# C2Sv0_-_Adaptor_TopLevel.net
KiCad netlist of a schematic drawn in Altium Designer
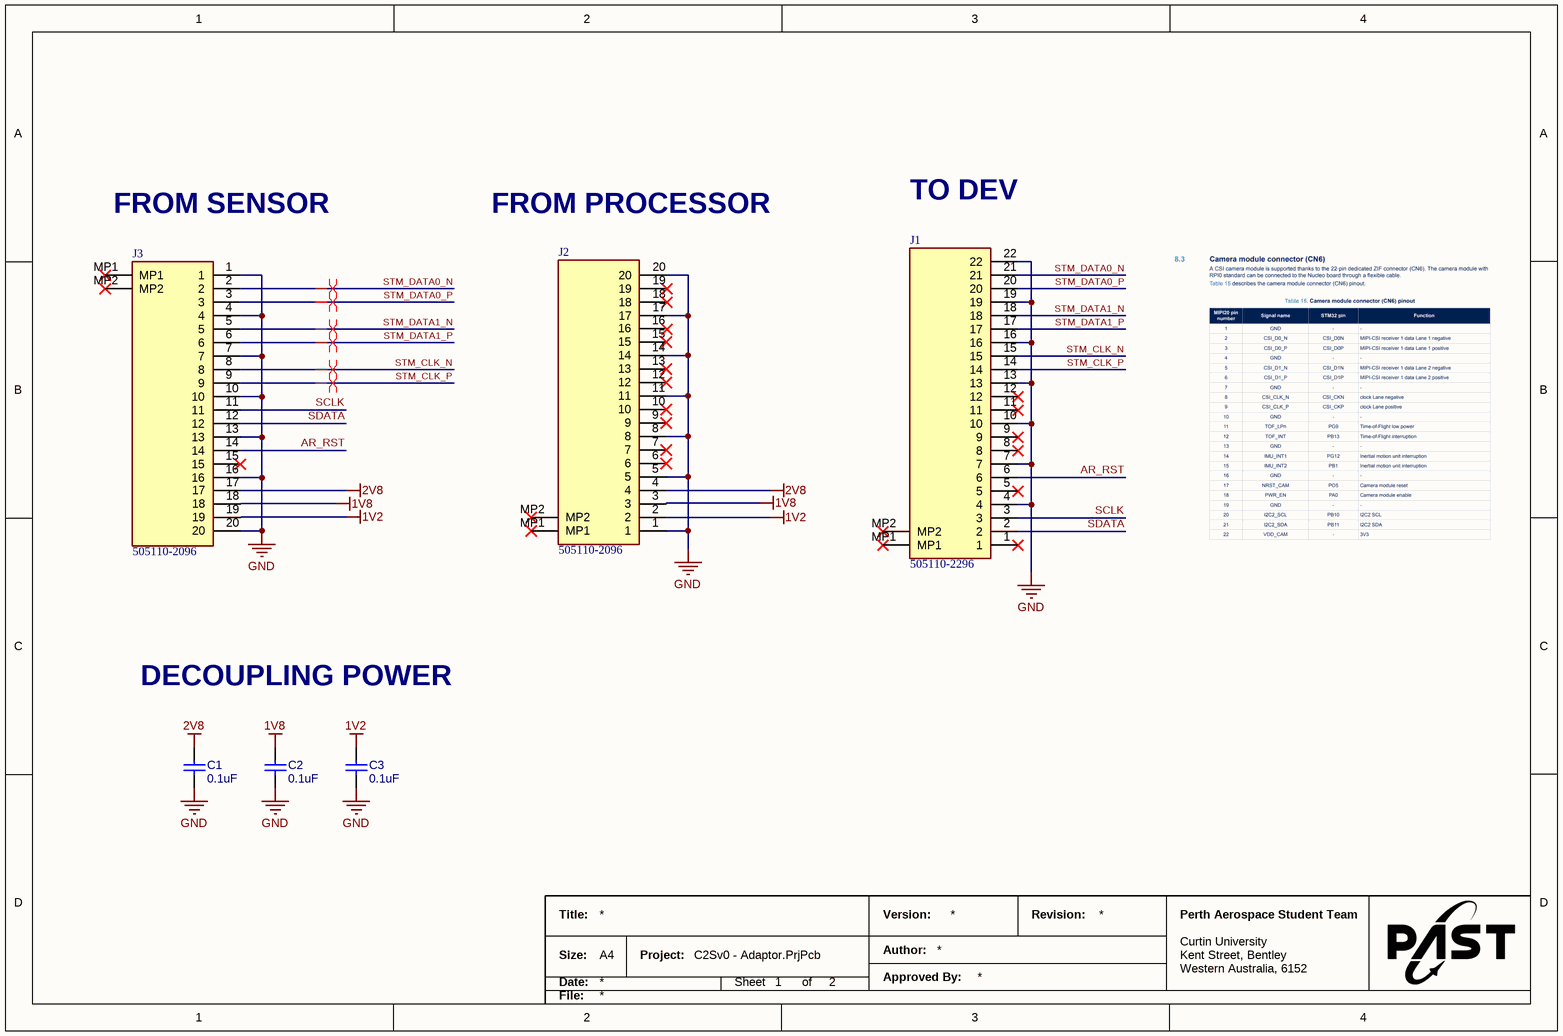
[diagram p0: C2Sv0 - Adaptor_TopLevel.SchDoc]

(export (version "E")
  (design (tool "Eeschema 10.0.6"))
  (components
    (comp (ref "C1")
      (value "0.1uF")
      (footprint "C0603")
      (description "Capacitor, MLCC, 100nF, 6V3, X5R, 10%, 0603, T=0,8mm")
      (fields
        (field (name "MANUFACTURER PART NUMBER") "CC0603KRX5R5BB104")
        (field (name "MANUFACTURER") "YAGEO")
        (field (name "PROVIDED_BY") "SUBCO")
      )
      (libsource (lib "Perth Aerospace Student Team") (part "CMP-035-000015-1"))
    )
    (comp (ref "C2")
      (value "0.1uF")
      (footprint "C0603")
      (description "Capacitor, MLCC, 100nF, 6V3, X5R, 10%, 0603, T=0,8mm")
      (fields
        (field (name "MANUFACTURER PART NUMBER") "CC0603KRX5R5BB104")
        (field (name "MANUFACTURER") "YAGEO")
        (field (name "PROVIDED_BY") "SUBCO")
      )
      (libsource (lib "Perth Aerospace Student Team") (part "CMP-035-000015-1"))
    )
    (comp (ref "C3")
      (value "0.1uF")
      (footprint "C0603")
      (description "Capacitor, MLCC, 100nF, 6V3, X5R, 10%, 0603, T=0,8mm")
      (fields
        (field (name "MANUFACTURER PART NUMBER") "CC0603KRX5R5BB104")
        (field (name "MANUFACTURER") "YAGEO")
        (field (name "PROVIDED_BY") "SUBCO")
      )
      (libsource (lib "Perth Aerospace Student Team") (part "CMP-035-000015-1"))
    )
    (comp (ref "J1")
      (value "505110-2296")
      (footprint "C2Sv0 - Adaptor:505110-2296")
      (description "Connector")
      (fields (field (name "MOUSER PART NUMBER") "538-505110-2296"))
      (libsource (lib "C2Sv0 - Adaptor") (part "505110-2296"))
    )
    (comp (ref "J2")
      (value "505110-2096")
      (footprint "505110-2096")
      (description "Connector")
      (fields (field (name "MOUSER PART NUMBER") "538-505110-2096"))
      (libsource (lib "C2Sv0 - Adaptor") (part "505110-2096"))
    )
    (comp (ref "J3")
      (value "505110-2096")
      (footprint "505110-2096")
      (description "Connector")
      (fields (field (name "MOUSER PART NUMBER") "538-505110-2096"))
      (libsource (lib "") (part "505110-2096_1"))
    )
  )
  (nets
    (net (code "1") (name "/AR_RST") (class "Default")
      (node (ref "J1") (pin "6") (pinfunction "6_6") (pintype "passive"))
      (node (ref "J3") (pin "14") (pinfunction "14_14") (pintype "passive"))
    )
    (net (code "2") (name "/SCLK") (class "Default")
      (node (ref "J1") (pin "3") (pinfunction "3_3") (pintype "passive"))
      (node (ref "J3") (pin "11") (pinfunction "11_11") (pintype "passive"))
    )
    (net (code "3") (name "/SDATA") (class "Default")
      (node (ref "J1") (pin "2") (pinfunction "2_2") (pintype "passive"))
      (node (ref "J3") (pin "12") (pinfunction "12_12") (pintype "passive"))
    )
    (net (code "4") (name "/STM_CLK_N") (class "Default")
      (node (ref "J1") (pin "15") (pinfunction "15_15") (pintype "passive"))
      (node (ref "J3") (pin "8") (pinfunction "8_8") (pintype "passive"))
    )
    (net (code "5") (name "/STM_CLK_P") (class "Default")
      (node (ref "J1") (pin "14") (pinfunction "14_14") (pintype "passive"))
      (node (ref "J3") (pin "9") (pinfunction "9_9") (pintype "passive"))
    )
    (net (code "6") (name "/STM_DATA0_N") (class "Default")
      (node (ref "J1") (pin "21") (pinfunction "21_21") (pintype "passive"))
      (node (ref "J3") (pin "2") (pinfunction "2_2") (pintype "passive"))
    )
    (net (code "7") (name "/STM_DATA0_P") (class "Default")
      (node (ref "J1") (pin "20") (pinfunction "20_20") (pintype "passive"))
      (node (ref "J3") (pin "3") (pinfunction "3_3") (pintype "passive"))
    )
    (net (code "8") (name "/STM_DATA1_N") (class "Default")
      (node (ref "J1") (pin "18") (pinfunction "18_18") (pintype "passive"))
      (node (ref "J3") (pin "5") (pinfunction "5_5") (pintype "passive"))
    )
    (net (code "9") (name "/STM_DATA1_P") (class "Default")
      (node (ref "J1") (pin "17") (pinfunction "17_17") (pintype "passive"))
      (node (ref "J3") (pin "6") (pinfunction "6_6") (pintype "passive"))
    )
    (net (code "10") (name "1V2") (class "Default")
      (node (ref "C3") (pin "2") (pinfunction "2_2") (pintype "passive"))
      (node (ref "J2") (pin "2") (pinfunction "2_2") (pintype "passive"))
      (node (ref "J3") (pin "19") (pinfunction "19_19") (pintype "passive"))
    )
    (net (code "11") (name "1V8") (class "Default")
      (node (ref "C2") (pin "2") (pinfunction "2_2") (pintype "passive"))
      (node (ref "J2") (pin "3") (pinfunction "3_3") (pintype "passive"))
      (node (ref "J3") (pin "18") (pinfunction "18_18") (pintype "passive"))
    )
    (net (code "12") (name "2V8") (class "Default")
      (node (ref "C1") (pin "2") (pinfunction "2_2") (pintype "passive"))
      (node (ref "J2") (pin "4") (pinfunction "4_4") (pintype "passive"))
      (node (ref "J3") (pin "17") (pinfunction "17_17") (pintype "passive"))
    )
    (net (code "13") (name "GND") (class "Default")
      (node (ref "C1") (pin "1") (pinfunction "1_1") (pintype "passive"))
      (node (ref "C2") (pin "1") (pinfunction "1_1") (pintype "passive"))
      (node (ref "C3") (pin "1") (pinfunction "1_1") (pintype "passive"))
      (node (ref "J1") (pin "10") (pinfunction "10_10") (pintype "passive"))
      (node (ref "J1") (pin "13") (pinfunction "13_13") (pintype "passive"))
      (node (ref "J1") (pin "16") (pinfunction "16_16") (pintype "passive"))
      (node (ref "J1") (pin "19") (pinfunction "19_19") (pintype "passive"))
      (node (ref "J1") (pin "22") (pinfunction "22_22") (pintype "passive"))
      (node (ref "J1") (pin "4") (pinfunction "4_4") (pintype "passive"))
      (node (ref "J1") (pin "7") (pinfunction "7_7") (pintype "passive"))
      (node (ref "J2") (pin "1") (pinfunction "1_1") (pintype "passive"))
      (node (ref "J2") (pin "11") (pinfunction "11_11") (pintype "passive"))
      (node (ref "J2") (pin "14") (pinfunction "14_14") (pintype "passive"))
      (node (ref "J2") (pin "17") (pinfunction "17_17") (pintype "passive"))
      (node (ref "J2") (pin "20") (pinfunction "20_20") (pintype "passive"))
      (node (ref "J2") (pin "5") (pinfunction "5_5") (pintype "passive"))
      (node (ref "J2") (pin "8") (pinfunction "8_8") (pintype "passive"))
      (node (ref "J3") (pin "1") (pinfunction "1_1") (pintype "passive"))
      (node (ref "J3") (pin "10") (pinfunction "10_10") (pintype "passive"))
      (node (ref "J3") (pin "13") (pinfunction "13_13") (pintype "passive"))
      (node (ref "J3") (pin "16") (pinfunction "16_16") (pintype "passive"))
      (node (ref "J3") (pin "20") (pinfunction "20_20") (pintype "passive"))
      (node (ref "J3") (pin "4") (pinfunction "4_4") (pintype "passive"))
      (node (ref "J3") (pin "7") (pinfunction "7_7") (pintype "passive"))
    )
    (net (code "14") (name "unconnected-(J1-Pad1)") (class "Default")
      (node (ref "J1") (pin "1") (pinfunction "1_1") (pintype "passive+no_connect"))
    )
    (net (code "15") (name "unconnected-(J1-Pad5)") (class "Default")
      (node (ref "J1") (pin "5") (pinfunction "5_5") (pintype "passive+no_connect"))
    )
    (net (code "16") (name "unconnected-(J1-Pad8)") (class "Default")
      (node (ref "J1") (pin "8") (pinfunction "8_8") (pintype "passive+no_connect"))
    )
    (net (code "17") (name "unconnected-(J1-Pad9)") (class "Default")
      (node (ref "J1") (pin "9") (pinfunction "9_9") (pintype "passive+no_connect"))
    )
    (net (code "18") (name "unconnected-(J1-Pad11)") (class "Default")
      (node (ref "J1") (pin "11") (pinfunction "11_11") (pintype "passive+no_connect"))
    )
    (net (code "19") (name "unconnected-(J1-Pad12)") (class "Default")
      (node (ref "J1") (pin "12") (pinfunction "12_12") (pintype "passive+no_connect"))
    )
    (net (code "20") (name "unconnected-(J1-PadMP1)") (class "Default")
      (node (ref "J1") (pin "MP1") (pinfunction "MP1_MP1") (pintype "passive+no_connect"))
    )
    (net (code "21") (name "unconnected-(J1-PadMP2)") (class "Default")
      (node (ref "J1") (pin "MP2") (pinfunction "MP2_MP2") (pintype "passive+no_connect"))
    )
    (net (code "22") (name "unconnected-(J2-Pad6)") (class "Default")
      (node (ref "J2") (pin "6") (pinfunction "6_6") (pintype "passive+no_connect"))
    )
    (net (code "23") (name "unconnected-(J2-Pad7)") (class "Default")
      (node (ref "J2") (pin "7") (pinfunction "7_7") (pintype "passive+no_connect"))
    )
    (net (code "24") (name "unconnected-(J2-Pad9)") (class "Default")
      (node (ref "J2") (pin "9") (pinfunction "9_9") (pintype "passive+no_connect"))
    )
    (net (code "25") (name "unconnected-(J2-Pad10)") (class "Default")
      (node (ref "J2") (pin "10") (pinfunction "10_10") (pintype "passive+no_connect"))
    )
    (net (code "26") (name "unconnected-(J2-Pad12)") (class "Default")
      (node (ref "J2") (pin "12") (pinfunction "12_12") (pintype "passive+no_connect"))
    )
    (net (code "27") (name "unconnected-(J2-Pad13)") (class "Default")
      (node (ref "J2") (pin "13") (pinfunction "13_13") (pintype "passive+no_connect"))
    )
    (net (code "28") (name "unconnected-(J2-Pad15)") (class "Default")
      (node (ref "J2") (pin "15") (pinfunction "15_15") (pintype "passive+no_connect"))
    )
    (net (code "29") (name "unconnected-(J2-Pad16)") (class "Default")
      (node (ref "J2") (pin "16") (pinfunction "16_16") (pintype "passive"))
    )
    (net (code "30") (name "unconnected-(J2-Pad18)") (class "Default")
      (node (ref "J2") (pin "18") (pinfunction "18_18") (pintype "passive+no_connect"))
    )
    (net (code "31") (name "unconnected-(J2-Pad19)") (class "Default")
      (node (ref "J2") (pin "19") (pinfunction "19_19") (pintype "passive+no_connect"))
    )
    (net (code "32") (name "unconnected-(J2-PadMP1)") (class "Default")
      (node (ref "J2") (pin "MP1") (pinfunction "MP1_MP1") (pintype "passive+no_connect"))
    )
    (net (code "33") (name "unconnected-(J2-PadMP2)") (class "Default")
      (node (ref "J2") (pin "MP2") (pinfunction "MP2_MP2") (pintype "passive+no_connect"))
    )
    (net (code "34") (name "unconnected-(J3-Pad15)") (class "Default")
      (node (ref "J3") (pin "15") (pinfunction "15_15") (pintype "passive+no_connect"))
    )
    (net (code "35") (name "unconnected-(J3-PadMP1)") (class "Default")
      (node (ref "J3") (pin "MP1") (pinfunction "MP1_MP1") (pintype "passive+no_connect"))
    )
    (net (code "36") (name "unconnected-(J3-PadMP2)") (class "Default")
      (node (ref "J3") (pin "MP2") (pinfunction "MP2_MP2") (pintype "passive+no_connect"))
    )
  )
)
